# H01R0_Backend.net
KiCad netlist of a schematic drawn in Altium Designer
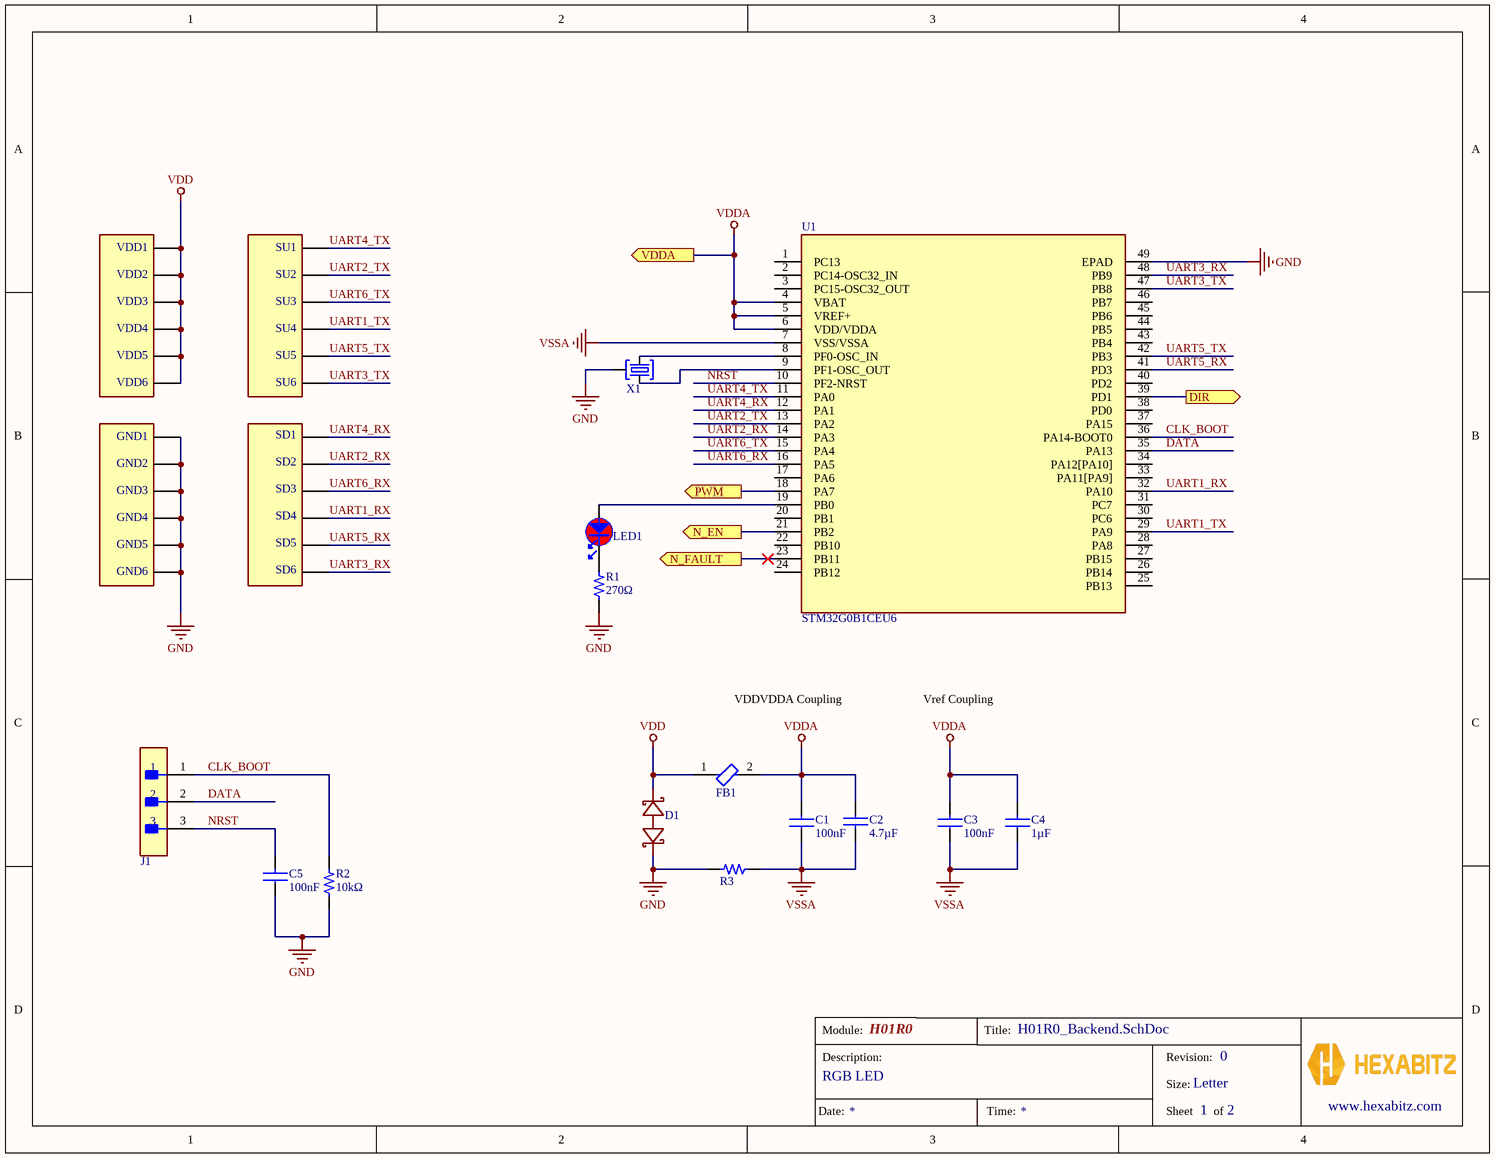
[diagram p0: H01R0_Backend.SchDoc]

(export (version "E")
  (design (tool "Eeschema 10.0.6"))
  (components
    (comp (ref "C1")
      (value "100nF")
      (footprint "C0603")
      (fields
        (field (name "MANUFACTURER") "Samsung Electro-Mechanics")
        (field (name "MANUFACTURER PART NUMBER") "CL10B104KA8NNNC")
        (field (name "TOLERANCE") "10%")
      )
      (libsource (lib "Hexabitz Altium Library") (part "generic Capacitor"))
    )
    (comp (ref "C2")
      (value "4.7µF")
      (footprint "C0805")
      (fields
        (field (name "MANUFACTURER") "Samsung Electro-Mechanics")
        (field (name "MANUFACTURER PART NUMBER") "CL21X475KAQNNNE")
        (field (name "TOLERANCE") "10%")
      )
      (libsource (lib "Hexabitz Altium Library") (part "generic Capacitor"))
    )
    (comp (ref "C3")
      (value "100nF")
      (footprint "C0603")
      (fields
        (field (name "MANUFACTURER") "Samsung Electro-Mechanics")
        (field (name "MANUFACTURER PART NUMBER") "CL10B104KA8NNNC")
        (field (name "TOLERANCE") "10%")
      )
      (libsource (lib "Hexabitz Altium Library") (part "generic Capacitor"))
    )
    (comp (ref "C4")
      (value "1µF")
      (footprint "C0805")
      (description "Ceramic Capacitor, Ceramic, 16V, 10% +Tol, 10% -Tol, X7R, 15% TC, 1uF, Surface Mount, 0805")
      (fields
        (field (name "MANUFACTURER") "Yageo Group")
        (field (name "MANUFACTURER PART NUMBER") "CC0805KKX7R7BB105")
      )
      (libsource (lib "Hexabitz Altium Library") (part "generic Capacitor"))
    )
    (comp (ref "C5")
      (value "100nF")
      (footprint "C0603")
      (fields
        (field (name "MANUFACTURER") "Samsung Electro-Mechanics")
        (field (name "MANUFACTURER PART NUMBER") "CL10B104KA8NNNC")
        (field (name "TOLERANCE") "10%")
      )
      (libsource (lib "Hexabitz Altium Library") (part "generic Capacitor"))
    )
    (comp (ref "D1")
      (value "CDSOD323-T03SC")
      (footprint "SOD2513X114N")
      (description "A 3V, 350W, bi-directional, standard capacitance, SOD323 pkg TVS Diode ¦ Bourns CDSOD323-T03SC")
      (fields (field (name "MANUFACTURER") "Bourns"))
      (libsource (lib "Hexabitz Altium Library") (part "CDSOD323-T03SC"))
    )
    (comp (ref "FB1")
      (value "MMZ1608Y300B")
      (footprint "FP-MMZ1608-0_8-MFG")
      (description "Ferrite Beads 0603 30ohms 1500mA Signal Line AEC-Q200")
      (fields
        (field (name "MANUFACTURER") "TDK")
        (field (name "MANUFACTURER PART NUMBER") "MMZ1608Y300BTD25")
      )
      (libsource (lib "Hexabitz Altium Library") (part "MMZ1608Y300B"))
    )
    (comp (ref "GND1")
      (value "HEXABIT_UART_PORT")
      (footprint "HEXABIT_POWER_PORT_D")
      (libsource (lib "hexabitz_connectors.Library") (part "HEXABIT_POWER_PORT_D"))
    )
    (comp (ref "GND2")
      (value "HEXABIT_UART_PORT")
      (footprint "HEXABIT_POWER_PORT_D")
      (libsource (lib "hexabitz_connectors.Library") (part "HEXABIT_POWER_PORT_D"))
    )
    (comp (ref "GND3")
      (value "HEXABIT_UART_PORT")
      (footprint "HEXABIT_POWER_PORT_D")
      (libsource (lib "hexabitz_connectors.Library") (part "HEXABIT_POWER_PORT_D"))
    )
    (comp (ref "GND4")
      (value "HEXABIT_UART_PORT")
      (footprint "HEXABIT_POWER_PORT_D")
      (libsource (lib "hexabitz_connectors.Library") (part "HEXABIT_POWER_PORT_D"))
    )
    (comp (ref "GND5")
      (value "HEXABIT_UART_PORT")
      (footprint "HEXABIT_POWER_PORT_D")
      (libsource (lib "hexabitz_connectors.Library") (part "HEXABIT_POWER_PORT_D"))
    )
    (comp (ref "GND6")
      (value "HEXABIT_UART_PORT")
      (footprint "HEXABIT_POWER_PORT_D")
      (libsource (lib "hexabitz_connectors.Library") (part "HEXABIT_POWER_PORT_D"))
    )
    (comp (ref "J1")
      (value "TSW-103-14-G-S")
      (footprint "FP-TSW-103-14-G-S-MFG")
      (description "CONN HEADER VERT 3POS 2.54MM")
      (libsource (lib "Altium Content Vault") (part "cd3439d6ef35ae5d9b27ec4fdd3e828"))
    )
    (comp (ref "LED1")
      (value "VLMS1300-GS08")
      (footprint "FP-6_541-5092_01-4-MFG")
      (description "LED Uni-Color Super Red 639nm 2-Pin Chip 0603(1608Metric) T/R")
      (fields (field (name "MANUFACTURER") "Vishay Semiconductors"))
      (libsource (lib "Hexabitz Altium Library") (part "VLMS1300-GS08"))
    )
    (comp (ref "R1")
      (value "270Ω")
      (footprint "R0603")
      (description "Res Thick Film 0603 270 Ohm 5% 0.1W(1/10W) ±200ppm/C Pad SMD Automotive T/R")
      (fields
        (field (name "MANUFACTURER") "Panasonic")
        (field (name "MANUFACTURER PART NUMBER") "ERJ-3GEYJ271V")
      )
      (libsource (lib "") (part "generic Resistor_2"))
    )
    (comp (ref "R2")
      (value "10kΩ")
      (footprint "R0603")
      (description "100mW Thick Film Resistors ±100ppm/℃ ±1% 10kΩ 0603 Chip Resistor - Surface Mount ROHS")
      (fields
        (field (name "MANUFACTURER") "Yageo Group")
        (field (name "MANUFACTURER PART NUMBER") "RC0603FR-0710KL")
      )
      (libsource (lib "Hexabitz Altium Library") (part "generic Resistor"))
    )
    (comp (ref "R3")
      (value "Manufacturer Part Number")
      (footprint "R0603")
      (libsource (lib "") (part "generic Resistor_1"))
    )
    (comp (ref "SD1")
      (value "HEXABIT_UART_PORT")
      (footprint "HEXABIT_UART_PORT_D")
      (libsource (lib "hexabitz_connectors.Library") (part "HEXABIT_UART_PORT_D"))
    )
    (comp (ref "SD2")
      (value "HEXABIT_UART_PORT")
      (footprint "HEXABIT_UART_PORT_D")
      (libsource (lib "hexabitz_connectors.Library") (part "HEXABIT_UART_PORT_D"))
    )
    (comp (ref "SD3")
      (value "HEXABIT_UART_PORT")
      (footprint "HEXABIT_UART_PORT_D")
      (libsource (lib "hexabitz_connectors.Library") (part "HEXABIT_UART_PORT_D"))
    )
    (comp (ref "SD4")
      (value "HEXABIT_UART_PORT")
      (footprint "HEXABIT_UART_PORT_D")
      (libsource (lib "hexabitz_connectors.Library") (part "HEXABIT_UART_PORT_D"))
    )
    (comp (ref "SD5")
      (value "HEXABIT_UART_PORT")
      (footprint "HEXABIT_UART_PORT_D")
      (libsource (lib "hexabitz_connectors.Library") (part "HEXABIT_UART_PORT_D"))
    )
    (comp (ref "SD6")
      (value "HEXABIT_UART_PORT")
      (footprint "HEXABIT_UART_PORT_D")
      (libsource (lib "hexabitz_connectors.Library") (part "HEXABIT_UART_PORT_D"))
    )
    (comp (ref "SU1")
      (value "HEXABIT_UART_PORT")
      (footprint "HEXABIT_UART_PORT_U")
      (libsource (lib "hexabitz_connectors.Library") (part "HEXABIT_UART_PORT_U"))
    )
    (comp (ref "SU2")
      (value "HEXABIT_UART_PORT")
      (footprint "HEXABIT_UART_PORT_U")
      (libsource (lib "hexabitz_connectors.Library") (part "HEXABIT_UART_PORT_U"))
    )
    (comp (ref "SU3")
      (value "HEXABIT_UART_PORT")
      (footprint "HEXABIT_UART_PORT_U")
      (libsource (lib "hexabitz_connectors.Library") (part "HEXABIT_UART_PORT_U"))
    )
    (comp (ref "SU4")
      (value "HEXABIT_UART_PORT")
      (footprint "HEXABIT_UART_PORT_U")
      (libsource (lib "hexabitz_connectors.Library") (part "HEXABIT_UART_PORT_U"))
    )
    (comp (ref "SU5")
      (value "HEXABIT_UART_PORT")
      (footprint "HEXABIT_UART_PORT_U")
      (libsource (lib "hexabitz_connectors.Library") (part "HEXABIT_UART_PORT_U"))
    )
    (comp (ref "SU6")
      (value "HEXABIT_UART_PORT")
      (footprint "HEXABIT_UART_PORT_U")
      (libsource (lib "hexabitz_connectors.Library") (part "HEXABIT_UART_PORT_U"))
    )
    (comp (ref "U1")
      (value "STM32G0B1CEU6")
      (footprint "QFN50P700X700X65-49N-D")
      (description "MCU 32-bit ARM Cortex M0+ RISC 512KB Flash 1.8V/2.5V/3.3V 48-Pin UFQFPN EP Tray")
      (fields
        (field (name "MANUFACTURER") "STMicroelectronics")
        (field (name "MANUFACTURER PART NUMBER") "STM32G0B1CEU6")
      )
      (libsource (lib "Hexabitz Altium Library") (part "STM32G0B1CEU6"))
    )
    (comp (ref "VDD1")
      (value "HEXABIT_UART_PORT")
      (footprint "HEXABIT_POWER_PORT_U")
      (libsource (lib "hexabitz_connectors.Library") (part "HEXABIT_POWER_PORT_U"))
    )
    (comp (ref "VDD2")
      (value "HEXABIT_UART_PORT")
      (footprint "HEXABIT_POWER_PORT_U")
      (libsource (lib "hexabitz_connectors.Library") (part "HEXABIT_POWER_PORT_U"))
    )
    (comp (ref "VDD3")
      (value "HEXABIT_UART_PORT")
      (footprint "HEXABIT_POWER_PORT_U")
      (libsource (lib "hexabitz_connectors.Library") (part "HEXABIT_POWER_PORT_U"))
    )
    (comp (ref "VDD4")
      (value "HEXABIT_UART_PORT")
      (footprint "HEXABIT_POWER_PORT_U")
      (libsource (lib "hexabitz_connectors.Library") (part "HEXABIT_POWER_PORT_U"))
    )
    (comp (ref "VDD5")
      (value "HEXABIT_UART_PORT")
      (footprint "HEXABIT_POWER_PORT_U")
      (libsource (lib "hexabitz_connectors.Library") (part "HEXABIT_POWER_PORT_U"))
    )
    (comp (ref "VDD6")
      (value "HEXABIT_UART_PORT")
      (footprint "HEXABIT_POWER_PORT_U")
      (libsource (lib "hexabitz_connectors.Library") (part "HEXABIT_POWER_PORT_U"))
    )
    (comp (ref "X1")
      (value "CSTCE8M00G52Z-R0")
      (footprint "XTALL_CSTCE8M00G52")
      (description "Ceramic Resonator 8MHz ±0.5% (Tol) ±0.2% (Stability) 10pF 40Ohm 3-Pin CSMD T/R")
      (fields (field (name "MANUFACTURER") "Murata") (field (name "TOLERANCE") "0.5%"))
      (libsource (lib "Hexabitz Altium Library") (part "CSTCE8M00G52Z-R0"))
    )
  )
  (nets
    (net (code "1") (name "/CLK_BOOT") (class "Default")
      (node (ref "J1") (pin "1") (pinfunction "1_1") (pintype "passive"))
      (node (ref "R2") (pin "1") (pinfunction "1_1") (pintype "passive"))
      (node (ref "U1") (pin "36") (pinfunction "PA14-BOOT0_36") (pintype "passive"))
    )
    (net (code "2") (name "/DATA") (class "Default")
      (node (ref "J1") (pin "2") (pinfunction "2_2") (pintype "passive"))
      (node (ref "U1") (pin "35") (pinfunction "PA13_35") (pintype "passive"))
    )
    (net (code "3") (name "/DIR") (class "Default")
      (node (ref "U1") (pin "39") (pinfunction "PD1_39") (pintype "passive"))
    )
    (net (code "4") (name "/NRST") (class "Default")
      (node (ref "C5") (pin "2") (pinfunction "2_2") (pintype "passive"))
      (node (ref "J1") (pin "3") (pinfunction "3_3") (pintype "passive"))
      (node (ref "U1") (pin "10") (pinfunction "PF2-NRST_10") (pintype "passive"))
    )
    (net (code "5") (name "/N_EN") (class "Default")
      (node (ref "U1") (pin "21") (pinfunction "PB2_21") (pintype "passive"))
    )
    (net (code "6") (name "/N_FAULT") (class "Default")
      (node (ref "U1") (pin "23") (pinfunction "PB11_23") (pintype "passive"))
    )
    (net (code "7") (name "/PWM") (class "Default")
      (node (ref "U1") (pin "18") (pinfunction "PA7_18") (pintype "passive"))
    )
    (net (code "8") (name "/UART1_RX") (class "Default")
      (node (ref "SD4") (pin "UART_D") (pinfunction "UART_D_UART_D") (pintype "passive"))
      (node (ref "U1") (pin "32") (pinfunction "PA10_32") (pintype "passive"))
    )
    (net (code "9") (name "/UART1_TX") (class "Default")
      (node (ref "SU4") (pin "UART_U") (pinfunction "UART_U_UART_U") (pintype "passive"))
      (node (ref "U1") (pin "29") (pinfunction "PA9_29") (pintype "passive"))
    )
    (net (code "10") (name "/UART2_RX") (class "Default")
      (node (ref "SD2") (pin "UART_D") (pinfunction "UART_D_UART_D") (pintype "passive"))
      (node (ref "U1") (pin "14") (pinfunction "PA3_14") (pintype "passive"))
    )
    (net (code "11") (name "/UART2_TX") (class "Default")
      (node (ref "SU2") (pin "UART_U") (pinfunction "UART_U_UART_U") (pintype "passive"))
      (node (ref "U1") (pin "13") (pinfunction "PA2_13") (pintype "passive"))
    )
    (net (code "12") (name "/UART3_RX") (class "Default")
      (node (ref "SD6") (pin "UART_D") (pinfunction "UART_D_UART_D") (pintype "passive"))
      (node (ref "U1") (pin "48") (pinfunction "PB9_48") (pintype "passive"))
    )
    (net (code "13") (name "/UART3_TX") (class "Default")
      (node (ref "SU6") (pin "UART_U") (pinfunction "UART_U_UART_U") (pintype "passive"))
      (node (ref "U1") (pin "47") (pinfunction "PB8_47") (pintype "passive"))
    )
    (net (code "14") (name "/UART4_RX") (class "Default")
      (node (ref "SD1") (pin "UART_D") (pinfunction "UART_D_UART_D") (pintype "passive"))
      (node (ref "U1") (pin "12") (pinfunction "PA1_12") (pintype "passive"))
    )
    (net (code "15") (name "/UART4_TX") (class "Default")
      (node (ref "SU1") (pin "UART_U") (pinfunction "UART_U_UART_U") (pintype "passive"))
      (node (ref "U1") (pin "11") (pinfunction "PA0_11") (pintype "passive"))
    )
    (net (code "16") (name "/UART5_RX") (class "Default")
      (node (ref "SD5") (pin "UART_D") (pinfunction "UART_D_UART_D") (pintype "passive"))
      (node (ref "U1") (pin "41") (pinfunction "PD3_41") (pintype "passive"))
    )
    (net (code "17") (name "/UART5_TX") (class "Default")
      (node (ref "SU5") (pin "UART_U") (pinfunction "UART_U_UART_U") (pintype "passive"))
      (node (ref "U1") (pin "42") (pinfunction "PB3_42") (pintype "passive"))
    )
    (net (code "18") (name "/UART6_RX") (class "Default")
      (node (ref "SD3") (pin "UART_D") (pinfunction "UART_D_UART_D") (pintype "passive"))
      (node (ref "U1") (pin "16") (pinfunction "PA5_16") (pintype "passive"))
    )
    (net (code "19") (name "/UART6_TX") (class "Default")
      (node (ref "SU3") (pin "UART_U") (pinfunction "UART_U_UART_U") (pintype "passive"))
      (node (ref "U1") (pin "15") (pinfunction "PA4_15") (pintype "passive"))
    )
    (net (code "20") (name "GND") (class "Default")
      (node (ref "C5") (pin "1") (pinfunction "1_1") (pintype "passive"))
      (node (ref "D1") (pin "1") (pinfunction "A_1") (pintype "passive"))
      (node (ref "GND1") (pin "Pwr_D") (pinfunction "Pwr_D_Pwr_D") (pintype "passive"))
      (node (ref "GND2") (pin "Pwr_D") (pinfunction "Pwr_D_Pwr_D") (pintype "passive"))
      (node (ref "GND3") (pin "Pwr_D") (pinfunction "Pwr_D_Pwr_D") (pintype "passive"))
      (node (ref "GND4") (pin "Pwr_D") (pinfunction "Pwr_D_Pwr_D") (pintype "passive"))
      (node (ref "GND5") (pin "Pwr_D") (pinfunction "Pwr_D_Pwr_D") (pintype "passive"))
      (node (ref "GND6") (pin "Pwr_D") (pinfunction "Pwr_D_Pwr_D") (pintype "passive"))
      (node (ref "R1") (pin "1") (pinfunction "1_1") (pintype "passive"))
      (node (ref "R2") (pin "2") (pinfunction "2_2") (pintype "passive"))
      (node (ref "R3") (pin "1") (pinfunction "1_1") (pintype "passive"))
      (node (ref "U1") (pin "49") (pinfunction "EPAD_49") (pintype "passive"))
      (node (ref "X1") (pin "P$2") (pinfunction "2_P$2") (pintype "passive"))
    )
    (net (code "21") (name "Net-(LED1-Pad1)") (class "Default")
      (node (ref "LED1") (pin "1") (pintype "passive"))
      (node (ref "R1") (pin "2") (pinfunction "2_2") (pintype "passive"))
    )
    (net (code "22") (name "Net-(U1-PB0)") (class "Default")
      (node (ref "LED1") (pin "2") (pintype "passive"))
      (node (ref "U1") (pin "19") (pinfunction "PB0_19") (pintype "passive"))
    )
    (net (code "23") (name "Net-(U1-PF0-OSC_IN)") (class "Default")
      (node (ref "U1") (pin "8") (pinfunction "PF0-OSC_IN_8") (pintype "passive"))
      (node (ref "X1") (pin "P$3") (pinfunction "3_P$3") (pintype "passive"))
    )
    (net (code "24") (name "Net-(U1-PF1-OSC_OUT)") (class "Default")
      (node (ref "U1") (pin "9") (pinfunction "PF1-OSC_OUT_9") (pintype "passive"))
      (node (ref "X1") (pin "P$1") (pinfunction "1_P$1") (pintype "passive"))
    )
    (net (code "25") (name "VDD") (class "Default")
      (node (ref "D1") (pin "2") (pinfunction "C_2") (pintype "passive"))
      (node (ref "FB1") (pin "1") (pinfunction "1_1") (pintype "passive"))
      (node (ref "VDD1") (pin "Pwr_U") (pinfunction "Pwr_U_Pwr_U") (pintype "passive"))
      (node (ref "VDD2") (pin "Pwr_U") (pinfunction "Pwr_U_Pwr_U") (pintype "passive"))
      (node (ref "VDD3") (pin "Pwr_U") (pinfunction "Pwr_U_Pwr_U") (pintype "passive"))
      (node (ref "VDD4") (pin "Pwr_U") (pinfunction "Pwr_U_Pwr_U") (pintype "passive"))
      (node (ref "VDD5") (pin "Pwr_U") (pinfunction "Pwr_U_Pwr_U") (pintype "passive"))
      (node (ref "VDD6") (pin "Pwr_U") (pinfunction "Pwr_U_Pwr_U") (pintype "passive"))
    )
    (net (code "26") (name "VDDA") (class "Default")
      (node (ref "C1") (pin "2") (pinfunction "2_2") (pintype "passive"))
      (node (ref "C2") (pin "1") (pinfunction "1_1") (pintype "passive"))
      (node (ref "C3") (pin "2") (pinfunction "2_2") (pintype "passive"))
      (node (ref "C4") (pin "2") (pinfunction "2_2") (pintype "passive"))
      (node (ref "FB1") (pin "2") (pinfunction "2_2") (pintype "passive"))
      (node (ref "U1") (pin "4") (pinfunction "VBAT_4") (pintype "passive"))
      (node (ref "U1") (pin "5") (pinfunction "VREF+_5") (pintype "passive"))
      (node (ref "U1") (pin "6") (pinfunction "VDD/VDDA_6") (pintype "passive"))
    )
    (net (code "27") (name "VSSA") (class "Default")
      (node (ref "C1") (pin "1") (pinfunction "1_1") (pintype "passive"))
      (node (ref "C2") (pin "2") (pinfunction "2_2") (pintype "passive"))
      (node (ref "C3") (pin "1") (pinfunction "1_1") (pintype "passive"))
      (node (ref "C4") (pin "1") (pinfunction "1_1") (pintype "passive"))
      (node (ref "R3") (pin "2") (pinfunction "2_2") (pintype "passive"))
      (node (ref "U1") (pin "7") (pinfunction "VSS/VSSA_7") (pintype "passive"))
    )
    (net (code "28") (name "unconnected-(U1-PA6-Pad17)") (class "Default")
      (node (ref "U1") (pin "17") (pinfunction "PA6_17") (pintype "passive"))
    )
    (net (code "29") (name "unconnected-(U1-PA8-Pad28)") (class "Default")
      (node (ref "U1") (pin "28") (pinfunction "PA8_28") (pintype "passive"))
    )
    (net (code "30") (name "unconnected-(U1-PA11[PA9]-Pad33)") (class "Default")
      (node (ref "U1") (pin "33") (pinfunction "PA11[PA9]_33") (pintype "passive"))
    )
    (net (code "31") (name "unconnected-(U1-PA12[PA10]-Pad34)") (class "Default")
      (node (ref "U1") (pin "34") (pinfunction "PA12[PA10]_34") (pintype "passive"))
    )
    (net (code "32") (name "unconnected-(U1-PA15-Pad37)") (class "Default")
      (node (ref "U1") (pin "37") (pinfunction "PA15_37") (pintype "passive"))
    )
    (net (code "33") (name "unconnected-(U1-PB1-Pad20)") (class "Default")
      (node (ref "U1") (pin "20") (pinfunction "PB1_20") (pintype "passive"))
    )
    (net (code "34") (name "unconnected-(U1-PB4-Pad43)") (class "Default")
      (node (ref "U1") (pin "43") (pinfunction "PB4_43") (pintype "passive"))
    )
    (net (code "35") (name "unconnected-(U1-PB5-Pad44)") (class "Default")
      (node (ref "U1") (pin "44") (pinfunction "PB5_44") (pintype "passive"))
    )
    (net (code "36") (name "unconnected-(U1-PB6-Pad45)") (class "Default")
      (node (ref "U1") (pin "45") (pinfunction "PB6_45") (pintype "passive"))
    )
    (net (code "37") (name "unconnected-(U1-PB7-Pad46)") (class "Default")
      (node (ref "U1") (pin "46") (pinfunction "PB7_46") (pintype "passive"))
    )
    (net (code "38") (name "unconnected-(U1-PB10-Pad22)") (class "Default")
      (node (ref "U1") (pin "22") (pinfunction "PB10_22") (pintype "passive"))
    )
    (net (code "39") (name "unconnected-(U1-PB12-Pad24)") (class "Default")
      (node (ref "U1") (pin "24") (pinfunction "PB12_24") (pintype "passive"))
    )
    (net (code "40") (name "unconnected-(U1-PB13-Pad25)") (class "Default")
      (node (ref "U1") (pin "25") (pinfunction "PB13_25") (pintype "passive"))
    )
    (net (code "41") (name "unconnected-(U1-PB14-Pad26)") (class "Default")
      (node (ref "U1") (pin "26") (pinfunction "PB14_26") (pintype "passive"))
    )
    (net (code "42") (name "unconnected-(U1-PB15-Pad27)") (class "Default")
      (node (ref "U1") (pin "27") (pinfunction "PB15_27") (pintype "passive"))
    )
    (net (code "43") (name "unconnected-(U1-PC6-Pad30)") (class "Default")
      (node (ref "U1") (pin "30") (pinfunction "PC6_30") (pintype "passive"))
    )
    (net (code "44") (name "unconnected-(U1-PC7-Pad31)") (class "Default")
      (node (ref "U1") (pin "31") (pinfunction "PC7_31") (pintype "passive"))
    )
    (net (code "45") (name "unconnected-(U1-PC13-Pad1)") (class "Default")
      (node (ref "U1") (pin "1") (pinfunction "PC13_1") (pintype "passive"))
    )
    (net (code "46") (name "unconnected-(U1-PC14-OSC32_IN-Pad2)") (class "Default")
      (node (ref "U1") (pin "2") (pinfunction "PC14-OSC32_IN_2") (pintype "passive"))
    )
    (net (code "47") (name "unconnected-(U1-PC15-OSC32_OUT-Pad3)") (class "Default")
      (node (ref "U1") (pin "3") (pinfunction "PC15-OSC32_OUT_3") (pintype "passive"))
    )
    (net (code "48") (name "unconnected-(U1-PD0-Pad38)") (class "Default")
      (node (ref "U1") (pin "38") (pinfunction "PD0_38") (pintype "passive"))
    )
    (net (code "49") (name "unconnected-(U1-PD2-Pad40)") (class "Default")
      (node (ref "U1") (pin "40") (pinfunction "PD2_40") (pintype "passive"))
    )
  )
)
